# bothsys.net
KiCad netlist of a schematic drawn in EAGLE
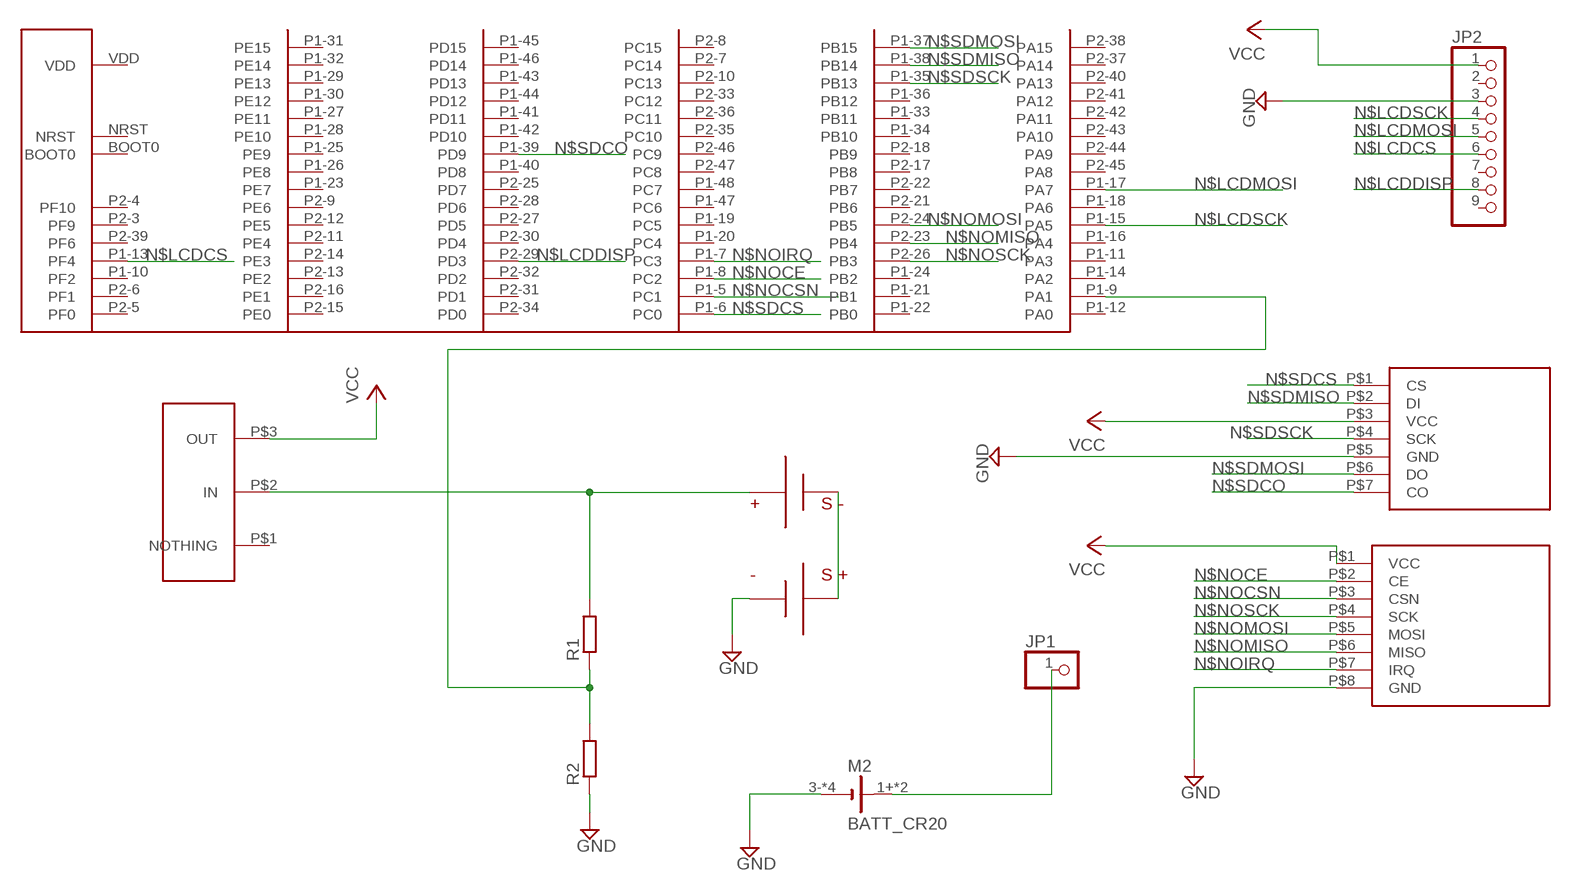
[diagram p0: schematic, sheet 1]

(export (version "E")
  (design (tool "Eeschema 10.0.6"))
  (components
    (comp (ref "JP1")
      (value "PINHD-1X1")
      (footprint "eagle-import:1X01")
      (libsource (lib "eagle-import") (part "PINHD-1X1"))
    )
    (comp (ref "JP2")
      (value "PINHD-1X9")
      (footprint "eagle-import:1X09")
      (libsource (lib "eagle-import") (part "PINHD-1X9"))
    )
    (comp (ref "M2")
      (value "BATT_CR20")
      (footprint "eagle-import:BATT_CR20")
      (libsource (lib "eagle-import") (part "BATT_CR20"))
    )
    (comp (ref "R1")
      (value "R-EU_R0805")
      (footprint "eagle-import:R0805")
      (libsource (lib "eagle-import") (part "R-EU_R0805"))
    )
    (comp (ref "R2")
      (value "R-EU_R0805")
      (footprint "eagle-import:R0805")
      (libsource (lib "eagle-import") (part "R-EU_R0805"))
    )
    (comp (ref "ST1")
      (value "STM32_F3")
      (footprint "eagle-import:STM32F3")
      (libsource (lib "eagle-import") (part "STM32_F3"))
    )
    (comp (ref "U$1")
      (value "SDCARD")
      (footprint "eagle-import:SDCARD")
      (libsource (lib "eagle-import") (part "SDCARD"))
    )
    (comp (ref "U$2")
      (value "NORDIC_NRF24L01")
      (footprint "eagle-import:NORDIC_NRF24L01")
      (libsource (lib "eagle-import") (part "NORDIC_NRF24L01"))
    )
    (comp (ref "U$3")
      (value "OS102011MA1QN1")
      (footprint "eagle-import:OS102011MA1QN1")
      (libsource (lib "eagle-import") (part "OS102011MA1QN1"))
    )
    (comp (ref "U$4")
      (value "OURBATT")
      (footprint "eagle-import:OURBATT")
      (libsource (lib "eagle-import") (part "OURBATT"))
    )
  )
  (nets
    (net (code "1") (name "/N$LCDCS") (class "Default")
      (node (ref "JP2") (pin "6") (pinfunction "6_6") (pintype "passive"))
      (node (ref "ST1") (pin "P1-13") (pinfunction "PF4_P1-13") (pintype "bidirectional"))
    )
    (net (code "2") (name "/N$LCDDISP") (class "Default")
      (node (ref "JP2") (pin "8") (pinfunction "8_8") (pintype "passive"))
      (node (ref "ST1") (pin "P2-29") (pinfunction "PD3_P2-29") (pintype "bidirectional"))
    )
    (net (code "3") (name "/N$LCDMOSI") (class "Default")
      (node (ref "JP2") (pin "5") (pinfunction "5_5") (pintype "passive"))
      (node (ref "ST1") (pin "P1-17") (pinfunction "PA7_P1-17") (pintype "bidirectional"))
    )
    (net (code "4") (name "/N$LCDSCK") (class "Default")
      (node (ref "JP2") (pin "4") (pinfunction "4_4") (pintype "passive"))
      (node (ref "ST1") (pin "P1-15") (pinfunction "PA5_P1-15") (pintype "bidirectional"))
    )
    (net (code "5") (name "/N$NOCE") (class "Default")
      (node (ref "ST1") (pin "P1-8") (pinfunction "PC2_P1-8") (pintype "bidirectional"))
      (node (ref "U$2") (pin "P$2") (pinfunction "CE_P$2") (pintype "bidirectional"))
    )
    (net (code "6") (name "/N$NOCSN") (class "Default")
      (node (ref "ST1") (pin "P1-5") (pinfunction "PC1_P1-5") (pintype "bidirectional"))
      (node (ref "U$2") (pin "P$3") (pinfunction "CSN_P$3") (pintype "bidirectional"))
    )
    (net (code "7") (name "/N$NOIRQ") (class "Default")
      (node (ref "ST1") (pin "P1-7") (pinfunction "PC3_P1-7") (pintype "bidirectional"))
      (node (ref "U$2") (pin "P$7") (pinfunction "IRQ_P$7") (pintype "bidirectional"))
    )
    (net (code "8") (name "/N$NOMISO") (class "Default")
      (node (ref "ST1") (pin "P2-23") (pinfunction "PB4_P2-23") (pintype "bidirectional"))
      (node (ref "U$2") (pin "P$6") (pinfunction "MISO_P$6") (pintype "bidirectional"))
    )
    (net (code "9") (name "/N$NOMOSI") (class "Default")
      (node (ref "ST1") (pin "P2-24") (pinfunction "PB5_P2-24") (pintype "bidirectional"))
      (node (ref "U$2") (pin "P$5") (pinfunction "MOSI_P$5") (pintype "bidirectional"))
    )
    (net (code "10") (name "/N$NOSCK") (class "Default")
      (node (ref "ST1") (pin "P2-26") (pinfunction "PB3_P2-26") (pintype "bidirectional"))
      (node (ref "U$2") (pin "P$4") (pinfunction "SCK_P$4") (pintype "bidirectional"))
    )
    (net (code "11") (name "/N$SDCO") (class "Default")
      (node (ref "ST1") (pin "P1-39") (pinfunction "PD9_P1-39") (pintype "bidirectional"))
      (node (ref "U$1") (pin "P$7") (pinfunction "CO_P$7") (pintype "bidirectional"))
    )
    (net (code "12") (name "/N$SDCS") (class "Default")
      (node (ref "ST1") (pin "P1-6") (pinfunction "PC0_P1-6") (pintype "bidirectional"))
      (node (ref "U$1") (pin "P$1") (pinfunction "CS_P$1") (pintype "bidirectional"))
    )
    (net (code "13") (name "/N$SDMISO") (class "Default")
      (node (ref "ST1") (pin "P1-38") (pinfunction "PB14_P1-38") (pintype "bidirectional"))
      (node (ref "U$1") (pin "P$2") (pinfunction "DI_P$2") (pintype "bidirectional"))
    )
    (net (code "14") (name "/N$SDMOSI") (class "Default")
      (node (ref "ST1") (pin "P1-37") (pinfunction "PB15_P1-37") (pintype "bidirectional"))
      (node (ref "U$1") (pin "P$6") (pinfunction "DO_P$6") (pintype "bidirectional"))
    )
    (net (code "15") (name "/N$SDSCK") (class "Default")
      (node (ref "ST1") (pin "P1-35") (pinfunction "PB13_P1-35") (pintype "bidirectional"))
      (node (ref "U$1") (pin "P$4") (pinfunction "SCK_P$4") (pintype "bidirectional"))
    )
    (net (code "16") (name "/VDD") (class "Default")
      (node (ref "ST1") (pin "VDD") (pinfunction "VDD_VDD") (pintype "power_in"))
    )
    (net (code "17") (name "GND") (class "Default")
      (node (ref "JP2") (pin "3") (pinfunction "3_3") (pintype "passive"))
      (node (ref "M2") (pin "3-") (pinfunction "-_3-") (pintype "passive"))
      (node (ref "M2") (pin "4-") (pinfunction "-_4-") (pintype "passive"))
      (node (ref "M2") (pin "5-") (pinfunction "-_5-") (pintype "passive"))
      (node (ref "M2") (pin "6-") (pinfunction "-_6-") (pintype "passive"))
      (node (ref "R2") (pin "1") (pinfunction "1_1") (pintype "passive"))
      (node (ref "U$1") (pin "P$5") (pinfunction "GND_P$5") (pintype "bidirectional"))
      (node (ref "U$2") (pin "P$8") (pinfunction "GND_P$8") (pintype "bidirectional"))
      (node (ref "U$4") (pin "-") (pinfunction "GROUND_-") (pintype "bidirectional"))
    )
    (net (code "18") (name "Net-(JP1-Pad1)") (class "Default")
      (node (ref "JP1") (pin "1") (pinfunction "1_1") (pintype "passive"))
      (node (ref "M2") (pin "1+") (pinfunction "+_1+") (pintype "passive"))
      (node (ref "M2") (pin "2+") (pinfunction "+_2+") (pintype "passive"))
    )
    (net (code "19") (name "Net-(ST1A-PA1)") (class "Default")
      (node (ref "R1") (pin "1") (pinfunction "1_1") (pintype "passive"))
      (node (ref "R2") (pin "2") (pinfunction "2_2") (pintype "passive"))
      (node (ref "ST1") (pin "P1-9") (pinfunction "PA1_P1-9") (pintype "bidirectional"))
    )
    (net (code "20") (name "Net-(U$3-IN)") (class "Default")
      (node (ref "R1") (pin "2") (pinfunction "2_2") (pintype "passive"))
      (node (ref "U$3") (pin "P$2") (pinfunction "IN_P$2") (pintype "bidirectional"))
      (node (ref "U$4") (pin "+") (pinfunction "POWER_+") (pintype "bidirectional"))
    )
    (net (code "21") (name "Net-(U$4-PadSERIESNEG)") (class "Default")
      (node (ref "U$4") (pin "SERIESNEG") (pinfunction "SERIESNEG_SERIESNEG") (pintype "bidirectional"))
      (node (ref "U$4") (pin "SERIESPOS") (pinfunction "SERIESPOS_SERIESPOS") (pintype "bidirectional"))
    )
    (net (code "22") (name "VCC") (class "Default")
      (node (ref "JP2") (pin "1") (pinfunction "1_1") (pintype "passive"))
      (node (ref "U$1") (pin "P$3") (pinfunction "VCC_P$3") (pintype "bidirectional"))
      (node (ref "U$2") (pin "P$1") (pinfunction "VCC_P$1") (pintype "bidirectional"))
      (node (ref "U$3") (pin "P$3") (pinfunction "OUT_P$3") (pintype "bidirectional"))
    )
    (net (code "23") (name "unconnected-(JP2-Pad2)") (class "Default")
      (node (ref "JP2") (pin "2") (pinfunction "2_2") (pintype "passive"))
    )
    (net (code "24") (name "unconnected-(JP2-Pad7)") (class "Default")
      (node (ref "JP2") (pin "7") (pinfunction "7_7") (pintype "passive"))
    )
    (net (code "25") (name "unconnected-(JP2-Pad9)") (class "Default")
      (node (ref "JP2") (pin "9") (pinfunction "9_9") (pintype "passive"))
    )
    (net (code "26") (name "unconnected-(ST1-PadBOOT0)") (class "Default")
      (node (ref "ST1") (pin "BOOT0") (pinfunction "BOOT0_BOOT0") (pintype "bidirectional"))
    )
    (net (code "27") (name "unconnected-(ST1-PadNRST)") (class "Default")
      (node (ref "ST1") (pin "NRST") (pinfunction "NRST_NRST") (pintype "bidirectional"))
    )
    (net (code "28") (name "unconnected-(ST1A-PA0-PadP1-12)") (class "Default")
      (node (ref "ST1") (pin "P1-12") (pinfunction "PA0_P1-12") (pintype "bidirectional"))
    )
    (net (code "29") (name "unconnected-(ST1A-PA2-PadP1-14)") (class "Default")
      (node (ref "ST1") (pin "P1-14") (pinfunction "PA2_P1-14") (pintype "bidirectional"))
    )
    (net (code "30") (name "unconnected-(ST1A-PA3-PadP1-11)") (class "Default")
      (node (ref "ST1") (pin "P1-11") (pinfunction "PA3_P1-11") (pintype "bidirectional"))
    )
    (net (code "31") (name "unconnected-(ST1A-PA4-PadP1-16)") (class "Default")
      (node (ref "ST1") (pin "P1-16") (pinfunction "PA4_P1-16") (pintype "bidirectional"))
    )
    (net (code "32") (name "unconnected-(ST1A-PA6-PadP1-18)") (class "Default")
      (node (ref "ST1") (pin "P1-18") (pinfunction "PA6_P1-18") (pintype "bidirectional"))
    )
    (net (code "33") (name "unconnected-(ST1A-PA8-PadP2-45)") (class "Default")
      (node (ref "ST1") (pin "P2-45") (pinfunction "PA8_P2-45") (pintype "bidirectional"))
    )
    (net (code "34") (name "unconnected-(ST1A-PA9-PadP2-44)") (class "Default")
      (node (ref "ST1") (pin "P2-44") (pinfunction "PA9_P2-44") (pintype "bidirectional"))
    )
    (net (code "35") (name "unconnected-(ST1A-PA10-PadP2-43)") (class "Default")
      (node (ref "ST1") (pin "P2-43") (pinfunction "PA10_P2-43") (pintype "bidirectional"))
    )
    (net (code "36") (name "unconnected-(ST1A-PA11-PadP2-42)") (class "Default")
      (node (ref "ST1") (pin "P2-42") (pinfunction "PA11_P2-42") (pintype "bidirectional"))
    )
    (net (code "37") (name "unconnected-(ST1A-PA12-PadP2-41)") (class "Default")
      (node (ref "ST1") (pin "P2-41") (pinfunction "PA12_P2-41") (pintype "bidirectional"))
    )
    (net (code "38") (name "unconnected-(ST1A-PA13-PadP2-40)") (class "Default")
      (node (ref "ST1") (pin "P2-40") (pinfunction "PA13_P2-40") (pintype "bidirectional"))
    )
    (net (code "39") (name "unconnected-(ST1A-PA14-PadP2-37)") (class "Default")
      (node (ref "ST1") (pin "P2-37") (pinfunction "PA14_P2-37") (pintype "bidirectional"))
    )
    (net (code "40") (name "unconnected-(ST1A-PA15-PadP2-38)") (class "Default")
      (node (ref "ST1") (pin "P2-38") (pinfunction "PA15_P2-38") (pintype "bidirectional"))
    )
    (net (code "41") (name "unconnected-(ST1A-PB0-PadP1-22)") (class "Default")
      (node (ref "ST1") (pin "P1-22") (pinfunction "PB0_P1-22") (pintype "bidirectional"))
    )
    (net (code "42") (name "unconnected-(ST1A-PB1-PadP1-21)") (class "Default")
      (node (ref "ST1") (pin "P1-21") (pinfunction "PB1_P1-21") (pintype "bidirectional"))
    )
    (net (code "43") (name "unconnected-(ST1A-PB2-PadP1-24)") (class "Default")
      (node (ref "ST1") (pin "P1-24") (pinfunction "PB2_P1-24") (pintype "bidirectional"))
    )
    (net (code "44") (name "unconnected-(ST1A-PB6-PadP2-21)") (class "Default")
      (node (ref "ST1") (pin "P2-21") (pinfunction "PB6_P2-21") (pintype "bidirectional"))
    )
    (net (code "45") (name "unconnected-(ST1A-PB7-PadP2-22)") (class "Default")
      (node (ref "ST1") (pin "P2-22") (pinfunction "PB7_P2-22") (pintype "bidirectional"))
    )
    (net (code "46") (name "unconnected-(ST1A-PB8-PadP2-17)") (class "Default")
      (node (ref "ST1") (pin "P2-17") (pinfunction "PB8_P2-17") (pintype "bidirectional"))
    )
    (net (code "47") (name "unconnected-(ST1A-PB9-PadP2-18)") (class "Default")
      (node (ref "ST1") (pin "P2-18") (pinfunction "PB9_P2-18") (pintype "bidirectional"))
    )
    (net (code "48") (name "unconnected-(ST1A-PB10-PadP1-34)") (class "Default")
      (node (ref "ST1") (pin "P1-34") (pinfunction "PB10_P1-34") (pintype "bidirectional"))
    )
    (net (code "49") (name "unconnected-(ST1A-PB11-PadP1-33)") (class "Default")
      (node (ref "ST1") (pin "P1-33") (pinfunction "PB11_P1-33") (pintype "bidirectional"))
    )
    (net (code "50") (name "unconnected-(ST1A-PB12-PadP1-36)") (class "Default")
      (node (ref "ST1") (pin "P1-36") (pinfunction "PB12_P1-36") (pintype "bidirectional"))
    )
    (net (code "51") (name "unconnected-(ST1A-PC4-PadP1-20)") (class "Default")
      (node (ref "ST1") (pin "P1-20") (pinfunction "PC4_P1-20") (pintype "bidirectional"))
    )
    (net (code "52") (name "unconnected-(ST1A-PC5-PadP1-19)") (class "Default")
      (node (ref "ST1") (pin "P1-19") (pinfunction "PC5_P1-19") (pintype "bidirectional"))
    )
    (net (code "53") (name "unconnected-(ST1A-PC6-PadP1-47)") (class "Default")
      (node (ref "ST1") (pin "P1-47") (pinfunction "PC6_P1-47") (pintype "bidirectional"))
    )
    (net (code "54") (name "unconnected-(ST1A-PC7-PadP1-48)") (class "Default")
      (node (ref "ST1") (pin "P1-48") (pinfunction "PC7_P1-48") (pintype "bidirectional"))
    )
    (net (code "55") (name "unconnected-(ST1A-PC8-PadP2-47)") (class "Default")
      (node (ref "ST1") (pin "P2-47") (pinfunction "PC8_P2-47") (pintype "bidirectional"))
    )
    (net (code "56") (name "unconnected-(ST1A-PC9-PadP2-46)") (class "Default")
      (node (ref "ST1") (pin "P2-46") (pinfunction "PC9_P2-46") (pintype "bidirectional"))
    )
    (net (code "57") (name "unconnected-(ST1A-PC10-PadP2-35)") (class "Default")
      (node (ref "ST1") (pin "P2-35") (pinfunction "PC10_P2-35") (pintype "bidirectional"))
    )
    (net (code "58") (name "unconnected-(ST1A-PC11-PadP2-36)") (class "Default")
      (node (ref "ST1") (pin "P2-36") (pinfunction "PC11_P2-36") (pintype "bidirectional"))
    )
    (net (code "59") (name "unconnected-(ST1A-PC12-PadP2-33)") (class "Default")
      (node (ref "ST1") (pin "P2-33") (pinfunction "PC12_P2-33") (pintype "bidirectional"))
    )
    (net (code "60") (name "unconnected-(ST1A-PC13-PadP2-10)") (class "Default")
      (node (ref "ST1") (pin "P2-10") (pinfunction "PC13_P2-10") (pintype "bidirectional"))
    )
    (net (code "61") (name "unconnected-(ST1A-PC14-PadP2-7)") (class "Default")
      (node (ref "ST1") (pin "P2-7") (pinfunction "PC14_P2-7") (pintype "bidirectional"))
    )
    (net (code "62") (name "unconnected-(ST1A-PC15-PadP2-8)") (class "Default")
      (node (ref "ST1") (pin "P2-8") (pinfunction "PC15_P2-8") (pintype "bidirectional"))
    )
    (net (code "63") (name "unconnected-(ST1A-PD0-PadP2-34)") (class "Default")
      (node (ref "ST1") (pin "P2-34") (pinfunction "PD0_P2-34") (pintype "bidirectional"))
    )
    (net (code "64") (name "unconnected-(ST1A-PD1-PadP2-31)") (class "Default")
      (node (ref "ST1") (pin "P2-31") (pinfunction "PD1_P2-31") (pintype "bidirectional"))
    )
    (net (code "65") (name "unconnected-(ST1A-PD2-PadP2-32)") (class "Default")
      (node (ref "ST1") (pin "P2-32") (pinfunction "PD2_P2-32") (pintype "bidirectional"))
    )
    (net (code "66") (name "unconnected-(ST1A-PD4-PadP2-30)") (class "Default")
      (node (ref "ST1") (pin "P2-30") (pinfunction "PD4_P2-30") (pintype "bidirectional"))
    )
    (net (code "67") (name "unconnected-(ST1A-PD5-PadP2-27)") (class "Default")
      (node (ref "ST1") (pin "P2-27") (pinfunction "PD5_P2-27") (pintype "bidirectional"))
    )
    (net (code "68") (name "unconnected-(ST1A-PD6-PadP2-28)") (class "Default")
      (node (ref "ST1") (pin "P2-28") (pinfunction "PD6_P2-28") (pintype "bidirectional"))
    )
    (net (code "69") (name "unconnected-(ST1A-PD7-PadP2-25)") (class "Default")
      (node (ref "ST1") (pin "P2-25") (pinfunction "PD7_P2-25") (pintype "bidirectional"))
    )
    (net (code "70") (name "unconnected-(ST1A-PD8-PadP1-40)") (class "Default")
      (node (ref "ST1") (pin "P1-40") (pinfunction "PD8_P1-40") (pintype "bidirectional"))
    )
    (net (code "71") (name "unconnected-(ST1A-PD10-PadP1-42)") (class "Default")
      (node (ref "ST1") (pin "P1-42") (pinfunction "PD10_P1-42") (pintype "bidirectional"))
    )
    (net (code "72") (name "unconnected-(ST1A-PD11-PadP1-41)") (class "Default")
      (node (ref "ST1") (pin "P1-41") (pinfunction "PD11_P1-41") (pintype "bidirectional"))
    )
    (net (code "73") (name "unconnected-(ST1A-PD12-PadP1-44)") (class "Default")
      (node (ref "ST1") (pin "P1-44") (pinfunction "PD12_P1-44") (pintype "bidirectional"))
    )
    (net (code "74") (name "unconnected-(ST1A-PD13-PadP1-43)") (class "Default")
      (node (ref "ST1") (pin "P1-43") (pinfunction "PD13_P1-43") (pintype "bidirectional"))
    )
    (net (code "75") (name "unconnected-(ST1A-PD14-PadP1-46)") (class "Default")
      (node (ref "ST1") (pin "P1-46") (pinfunction "PD14_P1-46") (pintype "bidirectional"))
    )
    (net (code "76") (name "unconnected-(ST1A-PD15-PadP1-45)") (class "Default")
      (node (ref "ST1") (pin "P1-45") (pinfunction "PD15_P1-45") (pintype "bidirectional"))
    )
    (net (code "77") (name "unconnected-(ST1A-PE0-PadP2-15)") (class "Default")
      (node (ref "ST1") (pin "P2-15") (pinfunction "PE0_P2-15") (pintype "bidirectional"))
    )
    (net (code "78") (name "unconnected-(ST1A-PE1-PadP2-16)") (class "Default")
      (node (ref "ST1") (pin "P2-16") (pinfunction "PE1_P2-16") (pintype "bidirectional"))
    )
    (net (code "79") (name "unconnected-(ST1A-PE2-PadP2-13)") (class "Default")
      (node (ref "ST1") (pin "P2-13") (pinfunction "PE2_P2-13") (pintype "bidirectional"))
    )
    (net (code "80") (name "unconnected-(ST1A-PE3-PadP2-14)") (class "Default")
      (node (ref "ST1") (pin "P2-14") (pinfunction "PE3_P2-14") (pintype "bidirectional"))
    )
    (net (code "81") (name "unconnected-(ST1A-PE4-PadP2-11)") (class "Default")
      (node (ref "ST1") (pin "P2-11") (pinfunction "PE4_P2-11") (pintype "bidirectional"))
    )
    (net (code "82") (name "unconnected-(ST1A-PE5-PadP2-12)") (class "Default")
      (node (ref "ST1") (pin "P2-12") (pinfunction "PE5_P2-12") (pintype "bidirectional"))
    )
    (net (code "83") (name "unconnected-(ST1A-PE6-PadP2-9)") (class "Default")
      (node (ref "ST1") (pin "P2-9") (pinfunction "PE6_P2-9") (pintype "bidirectional"))
    )
    (net (code "84") (name "unconnected-(ST1A-PE7-PadP1-23)") (class "Default")
      (node (ref "ST1") (pin "P1-23") (pinfunction "PE7_P1-23") (pintype "bidirectional"))
    )
    (net (code "85") (name "unconnected-(ST1A-PE8-PadP1-26)") (class "Default")
      (node (ref "ST1") (pin "P1-26") (pinfunction "PE8_P1-26") (pintype "bidirectional"))
    )
    (net (code "86") (name "unconnected-(ST1A-PE9-PadP1-25)") (class "Default")
      (node (ref "ST1") (pin "P1-25") (pinfunction "PE9_P1-25") (pintype "bidirectional"))
    )
    (net (code "87") (name "unconnected-(ST1A-PE10-PadP1-28)") (class "Default")
      (node (ref "ST1") (pin "P1-28") (pinfunction "PE10_P1-28") (pintype "bidirectional"))
    )
    (net (code "88") (name "unconnected-(ST1A-PE11-PadP1-27)") (class "Default")
      (node (ref "ST1") (pin "P1-27") (pinfunction "PE11_P1-27") (pintype "bidirectional"))
    )
    (net (code "89") (name "unconnected-(ST1A-PE12-PadP1-30)") (class "Default")
      (node (ref "ST1") (pin "P1-30") (pinfunction "PE12_P1-30") (pintype "bidirectional"))
    )
    (net (code "90") (name "unconnected-(ST1A-PE13-PadP1-29)") (class "Default")
      (node (ref "ST1") (pin "P1-29") (pinfunction "PE13_P1-29") (pintype "bidirectional"))
    )
    (net (code "91") (name "unconnected-(ST1A-PE14-PadP1-32)") (class "Default")
      (node (ref "ST1") (pin "P1-32") (pinfunction "PE14_P1-32") (pintype "bidirectional"))
    )
    (net (code "92") (name "unconnected-(ST1A-PE15-PadP1-31)") (class "Default")
      (node (ref "ST1") (pin "P1-31") (pinfunction "PE15_P1-31") (pintype "bidirectional"))
    )
    (net (code "93") (name "unconnected-(ST1A-PF0-PadP2-5)") (class "Default")
      (node (ref "ST1") (pin "P2-5") (pinfunction "PF0_P2-5") (pintype "bidirectional"))
    )
    (net (code "94") (name "unconnected-(ST1A-PF1-PadP2-6)") (class "Default")
      (node (ref "ST1") (pin "P2-6") (pinfunction "PF1_P2-6") (pintype "bidirectional"))
    )
    (net (code "95") (name "unconnected-(ST1A-PF2-PadP1-10)") (class "Default")
      (node (ref "ST1") (pin "P1-10") (pinfunction "PF2_P1-10") (pintype "bidirectional"))
    )
    (net (code "96") (name "unconnected-(ST1A-PF6-PadP2-39)") (class "Default")
      (node (ref "ST1") (pin "P2-39") (pinfunction "PF6_P2-39") (pintype "bidirectional"))
    )
    (net (code "97") (name "unconnected-(ST1A-PF9-PadP2-3)") (class "Default")
      (node (ref "ST1") (pin "P2-3") (pinfunction "PF9_P2-3") (pintype "bidirectional"))
    )
    (net (code "98") (name "unconnected-(ST1A-PF10-PadP2-4)") (class "Default")
      (node (ref "ST1") (pin "P2-4") (pinfunction "PF10_P2-4") (pintype "bidirectional"))
    )
    (net (code "99") (name "unconnected-(U$3-NOTHING-PadP$1)") (class "Default")
      (node (ref "U$3") (pin "P$1") (pinfunction "NOTHING_P$1") (pintype "bidirectional"))
    )
  )
)
